# Motherboard.net
KiCad netlist of a schematic drawn in EAGLE
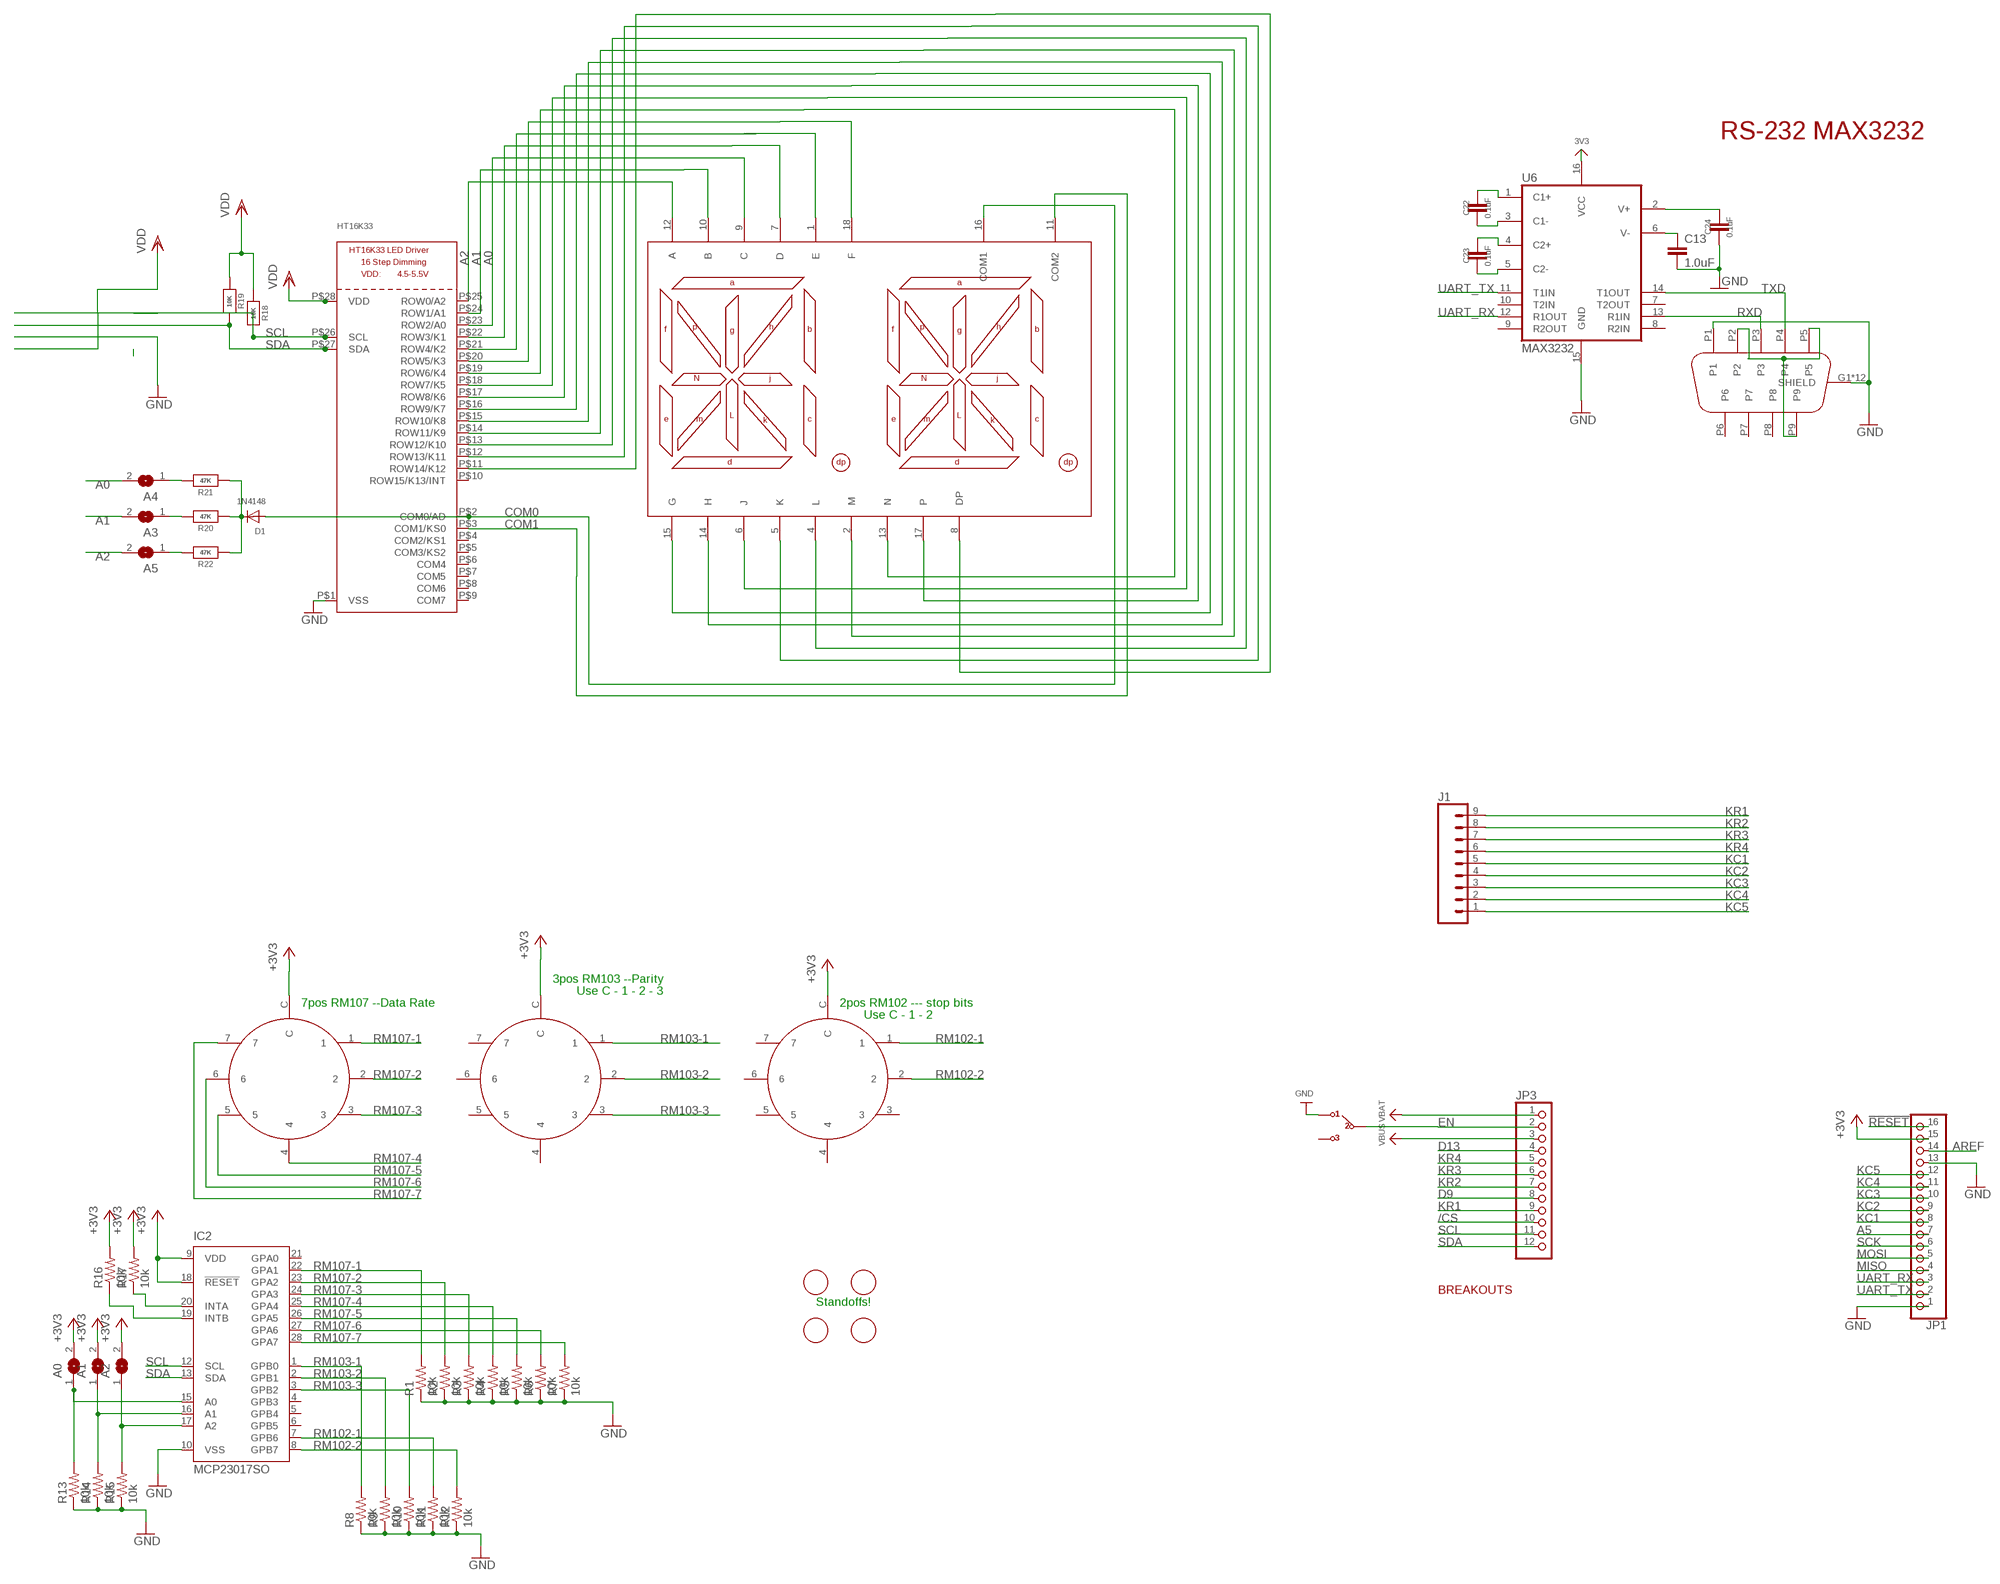
[diagram p0: schematic, sheet 1]

(export (version "E")
  (design (tool "Eeschema 10.0.6"))
  (components
    (comp (ref "A0") (value "SJ") (footprint "eagle-import:SJ") (libsource (lib "eagle-import") (part "SJ")))
    (comp (ref "A1") (value "SJ") (footprint "eagle-import:SJ") (libsource (lib "eagle-import") (part "SJ")))
    (comp (ref "A2") (value "SJ") (footprint "eagle-import:SJ") (libsource (lib "eagle-import") (part "SJ")))
    (comp (ref "A3")
      (value "SOLDERJUMPERREFLOW_NOPASTE")
      (footprint "eagle-import:SOLDERJUMPER_REFLOW_NOPASTE")
      (libsource (lib "eagle-import") (part "SOLDERJUMPERREFLOW_NOPASTE"))
    )
    (comp (ref "A4")
      (value "SOLDERJUMPERREFLOW_NOPASTE")
      (footprint "eagle-import:SOLDERJUMPER_REFLOW_NOPASTE")
      (libsource (lib "eagle-import") (part "SOLDERJUMPERREFLOW_NOPASTE"))
    )
    (comp (ref "A5")
      (value "SOLDERJUMPERREFLOW_NOPASTE")
      (footprint "eagle-import:SOLDERJUMPER_REFLOW_NOPASTE")
      (libsource (lib "eagle-import") (part "SOLDERJUMPERREFLOW_NOPASTE"))
    )
    (comp (ref "C13")
      (value "1.0uF")
      (footprint "eagle-import:0805")
      (libsource (lib "eagle-import") (part "1.0UF-0805-25V-10%"))
    )
    (comp (ref "C22")
      (value "0.1uF")
      (footprint "eagle-import:0805")
      (libsource (lib "eagle-import") (part "1.0UF-0805-25V-10%"))
    )
    (comp (ref "C23")
      (value "0.1uF")
      (footprint "eagle-import:0805")
      (libsource (lib "eagle-import") (part "1.0UF-0805-25V-10%"))
    )
    (comp (ref "C24")
      (value "0.1uF")
      (footprint "eagle-import:0805")
      (libsource (lib "eagle-import") (part "1.0UF-0805-25V-10%"))
    )
    (comp (ref "D1")
      (value "1N4148")
      (footprint "eagle-import:SOD-323F")
      (libsource (lib "eagle-import") (part "DIODESOD-323F"))
    )
    (comp (ref "DE9FEMALE")
      (value "EDGEMOUNTDE9")
      (footprint "eagle-import:DE09S065TLF")
      (libsource (lib "eagle-import") (part "EDGEMOUNTDE9"))
    )
    (comp (ref "HT16K33")
      (value "HT16K33_SOP28_SKINNY")
      (footprint "eagle-import:SOP28_300MIL_SKINNY")
      (libsource (lib "eagle-import") (part "HT16K33_SOP28_SKINNY"))
    )
    (comp (ref "IC2")
      (value "MCP23017SO")
      (footprint "eagle-import:SO28W")
      (libsource (lib "eagle-import") (part "MCP23017SO"))
    )
    (comp (ref "J1")
      (value "CONN_09")
      (footprint "eagle-import:1X09")
      (libsource (lib "eagle-import") (part "CONN_09"))
    )
    (comp (ref "JP1")
      (value "HEADER-1X16ROUND")
      (footprint "eagle-import:1X16_ROUND")
      (libsource (lib "eagle-import") (part "HEADER-1X16ROUND"))
    )
    (comp (ref "JP3")
      (value "HEADER-1X12")
      (footprint "eagle-import:1X12_ROUND")
      (libsource (lib "eagle-import") (part "HEADER-1X12"))
    )
    (comp (ref "R1")
      (value "10k")
      (footprint "eagle-import:M0805")
      (libsource (lib "eagle-import") (part "R-US_M0805"))
    )
    (comp (ref "R2")
      (value "10k")
      (footprint "eagle-import:M0805")
      (libsource (lib "eagle-import") (part "R-US_M0805"))
    )
    (comp (ref "R3")
      (value "10k")
      (footprint "eagle-import:M0805")
      (libsource (lib "eagle-import") (part "R-US_M0805"))
    )
    (comp (ref "R4")
      (value "10k")
      (footprint "eagle-import:M0805")
      (libsource (lib "eagle-import") (part "R-US_M0805"))
    )
    (comp (ref "R5")
      (value "10k")
      (footprint "eagle-import:M0805")
      (libsource (lib "eagle-import") (part "R-US_M0805"))
    )
    (comp (ref "R6")
      (value "10k")
      (footprint "eagle-import:M0805")
      (libsource (lib "eagle-import") (part "R-US_M0805"))
    )
    (comp (ref "R7")
      (value "10k")
      (footprint "eagle-import:M0805")
      (libsource (lib "eagle-import") (part "R-US_M0805"))
    )
    (comp (ref "R8")
      (value "10k")
      (footprint "eagle-import:M0805")
      (libsource (lib "eagle-import") (part "R-US_M0805"))
    )
    (comp (ref "R9")
      (value "10k")
      (footprint "eagle-import:M0805")
      (libsource (lib "eagle-import") (part "R-US_M0805"))
    )
    (comp (ref "R10")
      (value "10k")
      (footprint "eagle-import:M0805")
      (libsource (lib "eagle-import") (part "R-US_M0805"))
    )
    (comp (ref "R11")
      (value "10k")
      (footprint "eagle-import:M0805")
      (libsource (lib "eagle-import") (part "R-US_M0805"))
    )
    (comp (ref "R12")
      (value "10k")
      (footprint "eagle-import:M0805")
      (libsource (lib "eagle-import") (part "R-US_M0805"))
    )
    (comp (ref "R13")
      (value "10k")
      (footprint "eagle-import:M0805")
      (libsource (lib "eagle-import") (part "R-US_M0805"))
    )
    (comp (ref "R14")
      (value "10k")
      (footprint "eagle-import:M0805")
      (libsource (lib "eagle-import") (part "R-US_M0805"))
    )
    (comp (ref "R15")
      (value "10k")
      (footprint "eagle-import:M0805")
      (libsource (lib "eagle-import") (part "R-US_M0805"))
    )
    (comp (ref "R16")
      (value "10k")
      (footprint "eagle-import:M0805")
      (libsource (lib "eagle-import") (part "R-US_M0805"))
    )
    (comp (ref "R17")
      (value "10k")
      (footprint "eagle-import:M0805")
      (libsource (lib "eagle-import") (part "R-US_M0805"))
    )
    (comp (ref "R18")
      (value "10K")
      (footprint "eagle-import:0805-NO")
      (libsource (lib "eagle-import") (part "RESISTOR0805_NOOUTLINE"))
    )
    (comp (ref "R19")
      (value "10K")
      (footprint "eagle-import:0805-NO")
      (libsource (lib "eagle-import") (part "RESISTOR0805_NOOUTLINE"))
    )
    (comp (ref "R20")
      (value "47K")
      (footprint "eagle-import:0805-NO")
      (libsource (lib "eagle-import") (part "RESISTOR0805_NOOUTLINE"))
    )
    (comp (ref "R21")
      (value "47K")
      (footprint "eagle-import:0805-NO")
      (libsource (lib "eagle-import") (part "RESISTOR0805_NOOUTLINE"))
    )
    (comp (ref "R22")
      (value "47K")
      (footprint "eagle-import:0805-NO")
      (libsource (lib "eagle-import") (part "RESISTOR0805_NOOUTLINE"))
    )
    (comp (ref "U$1")
      (value "HDSP-A27C")
      (footprint "eagle-import:DIP-18")
      (libsource (lib "eagle-import") (part "HDSP-A27C"))
    )
    (comp (ref "U$2")
      (value "RM107772BCB")
      (footprint "eagle-import:RM107772BCB")
      (libsource (lib "eagle-import") (part "RM107772BCB"))
    )
    (comp (ref "U$3")
      (value "RM107772BCB")
      (footprint "eagle-import:RM107772BCB")
      (libsource (lib "eagle-import") (part "RM107772BCB"))
    )
    (comp (ref "U$5")
      (value "OS102011MA1QN1")
      (footprint "eagle-import:OS102011MA1QN1")
      (libsource (lib "eagle-import") (part "OS102011MA1QN1"))
    )
    (comp (ref "U$6")
      (value "RM107772BCB")
      (footprint "eagle-import:RM107772BCB")
      (libsource (lib "eagle-import") (part "RM107772BCB"))
    )
    (comp (ref "U$7")
      (value "KEYSTONESTANDOFF")
      (footprint "eagle-import:KEYSTONESTANDOFF")
      (libsource (lib "eagle-import") (part "KEYSTONESTANDOFF"))
    )
    (comp (ref "U$8")
      (value "KEYSTONESTANDOFF")
      (footprint "eagle-import:KEYSTONESTANDOFF")
      (libsource (lib "eagle-import") (part "KEYSTONESTANDOFF"))
    )
    (comp (ref "U$9")
      (value "KEYSTONESTANDOFF")
      (footprint "eagle-import:KEYSTONESTANDOFF")
      (libsource (lib "eagle-import") (part "KEYSTONESTANDOFF"))
    )
    (comp (ref "U$10")
      (value "KEYSTONESTANDOFF")
      (footprint "eagle-import:KEYSTONESTANDOFF")
      (libsource (lib "eagle-import") (part "KEYSTONESTANDOFF"))
    )
    (comp (ref "U6")
      (value "MAX3232")
      (footprint "eagle-import:SO16")
      (libsource (lib "eagle-import") (part "MAX2323SOIC16"))
    )
  )
  (nets
    (net (code "1") (name "+3V3") (class "Default")
      (node (ref "A0") (pin "2") (pinfunction "2_2") (pintype "passive"))
      (node (ref "A1") (pin "2") (pinfunction "2_2") (pintype "passive"))
      (node (ref "A2") (pin "2") (pinfunction "2_2") (pintype "passive"))
      (node (ref "IC2") (pin "18") (pinfunction "~{RESET}_18") (pintype "input"))
      (node (ref "IC2") (pin "9") (pinfunction "VDD_9") (pintype "power_in"))
      (node (ref "JP1") (pin "15") (pinfunction "15_15") (pintype "passive"))
      (node (ref "R16") (pin "2") (pinfunction "2_2") (pintype "passive"))
      (node (ref "R17") (pin "2") (pinfunction "2_2") (pintype "passive"))
      (node (ref "U$2") (pin "C") (pinfunction "C_C") (pintype "bidirectional"))
      (node (ref "U$3") (pin "C") (pinfunction "C_C") (pintype "bidirectional"))
      (node (ref "U$6") (pin "C") (pinfunction "C_C") (pintype "bidirectional"))
    )
    (net (code "2") (name "/A0") (class "Default")
      (node (ref "A4") (pin "2") (pinfunction "2_2") (pintype "passive"))
      (node (ref "HT16K33") (pin "P$23") (pinfunction "ROW2/A0_P$23") (pintype "bidirectional"))
      (node (ref "U$1") (pin "9") (pinfunction "C_9") (pintype "bidirectional"))
    )
    (net (code "3") (name "/A1") (class "Default")
      (node (ref "A3") (pin "2") (pinfunction "2_2") (pintype "passive"))
      (node (ref "HT16K33") (pin "P$24") (pinfunction "ROW1/A1_P$24") (pintype "bidirectional"))
      (node (ref "U$1") (pin "10") (pinfunction "B_10") (pintype "bidirectional"))
    )
    (net (code "4") (name "/A2") (class "Default")
      (node (ref "A5") (pin "2") (pinfunction "2_2") (pintype "passive"))
      (node (ref "HT16K33") (pin "P$25") (pinfunction "ROW0/A2_P$25") (pintype "bidirectional"))
      (node (ref "U$1") (pin "12") (pinfunction "A_12") (pintype "bidirectional"))
    )
    (net (code "5") (name "/A5") (class "Default")
      (node (ref "JP1") (pin "7") (pinfunction "7_7") (pintype "passive"))
    )
    (net (code "6") (name "/AREF") (class "Default")
      (node (ref "JP1") (pin "14") (pinfunction "14_14") (pintype "passive"))
    )
    (net (code "7") (name "/COM0") (class "Default")
      (node (ref "D1") (pin "A") (pinfunction "A_A") (pintype "passive"))
      (node (ref "HT16K33") (pin "P$2") (pinfunction "COM0/AD_P$2") (pintype "bidirectional"))
      (node (ref "U$1") (pin "16") (pinfunction "COM1_16") (pintype "bidirectional"))
    )
    (net (code "8") (name "/COM1") (class "Default")
      (node (ref "HT16K33") (pin "P$3") (pinfunction "COM1/KS0_P$3") (pintype "bidirectional"))
      (node (ref "U$1") (pin "11") (pinfunction "COM2_11") (pintype "bidirectional"))
    )
    (net (code "9") (name "/D9") (class "Default")
      (node (ref "JP3") (pin "8") (pinfunction "8_8") (pintype "passive"))
    )
    (net (code "10") (name "/D13") (class "Default")
      (node (ref "JP3") (pin "4") (pinfunction "4_4") (pintype "passive"))
    )
    (net (code "11") (name "/EN") (class "Default")
      (node (ref "JP3") (pin "2") (pinfunction "2_2") (pintype "passive"))
      (node (ref "U$5") (pin "P$2") (pinfunction "P$2_P$2") (pintype "bidirectional"))
    )
    (net (code "12") (name "/KC1") (class "Default")
      (node (ref "J1") (pin "5") (pinfunction "5_5") (pintype "passive"))
      (node (ref "JP1") (pin "8") (pinfunction "8_8") (pintype "passive"))
    )
    (net (code "13") (name "/KC2") (class "Default")
      (node (ref "J1") (pin "4") (pinfunction "4_4") (pintype "passive"))
      (node (ref "JP1") (pin "9") (pinfunction "9_9") (pintype "passive"))
    )
    (net (code "14") (name "/KC3") (class "Default")
      (node (ref "J1") (pin "3") (pinfunction "3_3") (pintype "passive"))
      (node (ref "JP1") (pin "10") (pinfunction "10_10") (pintype "passive"))
    )
    (net (code "15") (name "/KC4") (class "Default")
      (node (ref "J1") (pin "2") (pinfunction "2_2") (pintype "passive"))
      (node (ref "JP1") (pin "11") (pinfunction "11_11") (pintype "passive"))
    )
    (net (code "16") (name "/KC5") (class "Default")
      (node (ref "J1") (pin "1") (pinfunction "1_1") (pintype "passive"))
      (node (ref "JP1") (pin "12") (pinfunction "12_12") (pintype "passive"))
    )
    (net (code "17") (name "/KR1") (class "Default")
      (node (ref "J1") (pin "9") (pinfunction "9_9") (pintype "passive"))
      (node (ref "JP3") (pin "9") (pinfunction "9_9") (pintype "passive"))
    )
    (net (code "18") (name "/KR2") (class "Default")
      (node (ref "J1") (pin "8") (pinfunction "8_8") (pintype "passive"))
      (node (ref "JP3") (pin "7") (pinfunction "7_7") (pintype "passive"))
    )
    (net (code "19") (name "/KR3") (class "Default")
      (node (ref "J1") (pin "7") (pinfunction "7_7") (pintype "passive"))
      (node (ref "JP3") (pin "6") (pinfunction "6_6") (pintype "passive"))
    )
    (net (code "20") (name "/KR4") (class "Default")
      (node (ref "J1") (pin "6") (pinfunction "6_6") (pintype "passive"))
      (node (ref "JP3") (pin "5") (pinfunction "5_5") (pintype "passive"))
    )
    (net (code "21") (name "/MISO") (class "Default")
      (node (ref "JP1") (pin "4") (pinfunction "4_4") (pintype "passive"))
    )
    (net (code "22") (name "/MOSI") (class "Default")
      (node (ref "JP1") (pin "5") (pinfunction "5_5") (pintype "passive"))
    )
    (net (code "23") (name "/RM102-1") (class "Default")
      (node (ref "IC2") (pin "7") (pinfunction "GPB6_7") (pintype "bidirectional"))
      (node (ref "R11") (pin "2") (pinfunction "2_2") (pintype "passive"))
      (node (ref "U$6") (pin "1") (pinfunction "1_1") (pintype "bidirectional"))
    )
    (net (code "24") (name "/RM102-2") (class "Default")
      (node (ref "IC2") (pin "8") (pinfunction "GPB7_8") (pintype "bidirectional"))
      (node (ref "R12") (pin "2") (pinfunction "2_2") (pintype "passive"))
      (node (ref "U$6") (pin "2") (pinfunction "2_2") (pintype "bidirectional"))
    )
    (net (code "25") (name "/RM103-1") (class "Default")
      (node (ref "IC2") (pin "1") (pinfunction "GPB0_1") (pintype "bidirectional"))
      (node (ref "R8") (pin "2") (pinfunction "2_2") (pintype "passive"))
      (node (ref "U$3") (pin "1") (pinfunction "1_1") (pintype "bidirectional"))
    )
    (net (code "26") (name "/RM103-2") (class "Default")
      (node (ref "IC2") (pin "2") (pinfunction "GPB1_2") (pintype "bidirectional"))
      (node (ref "R9") (pin "2") (pinfunction "2_2") (pintype "passive"))
      (node (ref "U$3") (pin "2") (pinfunction "2_2") (pintype "bidirectional"))
    )
    (net (code "27") (name "/RM103-3") (class "Default")
      (node (ref "IC2") (pin "3") (pinfunction "GPB2_3") (pintype "bidirectional"))
      (node (ref "R10") (pin "2") (pinfunction "2_2") (pintype "passive"))
      (node (ref "U$3") (pin "3") (pinfunction "3_3") (pintype "bidirectional"))
    )
    (net (code "28") (name "/RM107-1") (class "Default")
      (node (ref "IC2") (pin "22") (pinfunction "GPA1_22") (pintype "bidirectional"))
      (node (ref "R1") (pin "2") (pinfunction "2_2") (pintype "passive"))
      (node (ref "U$2") (pin "1") (pinfunction "1_1") (pintype "bidirectional"))
    )
    (net (code "29") (name "/RM107-2") (class "Default")
      (node (ref "IC2") (pin "23") (pinfunction "GPA2_23") (pintype "bidirectional"))
      (node (ref "R2") (pin "2") (pinfunction "2_2") (pintype "passive"))
      (node (ref "U$2") (pin "2") (pinfunction "2_2") (pintype "bidirectional"))
    )
    (net (code "30") (name "/RM107-3") (class "Default")
      (node (ref "IC2") (pin "24") (pinfunction "GPA3_24") (pintype "bidirectional"))
      (node (ref "R3") (pin "2") (pinfunction "2_2") (pintype "passive"))
      (node (ref "U$2") (pin "3") (pinfunction "3_3") (pintype "bidirectional"))
    )
    (net (code "31") (name "/RM107-4") (class "Default")
      (node (ref "IC2") (pin "25") (pinfunction "GPA4_25") (pintype "bidirectional"))
      (node (ref "R4") (pin "2") (pinfunction "2_2") (pintype "passive"))
      (node (ref "U$2") (pin "4") (pinfunction "4_4") (pintype "bidirectional"))
    )
    (net (code "32") (name "/RM107-5") (class "Default")
      (node (ref "IC2") (pin "26") (pinfunction "GPA5_26") (pintype "bidirectional"))
      (node (ref "R5") (pin "2") (pinfunction "2_2") (pintype "passive"))
      (node (ref "U$2") (pin "5") (pinfunction "5_5") (pintype "bidirectional"))
    )
    (net (code "33") (name "/RM107-6") (class "Default")
      (node (ref "IC2") (pin "27") (pinfunction "GPA6_27") (pintype "bidirectional"))
      (node (ref "R6") (pin "2") (pinfunction "2_2") (pintype "passive"))
      (node (ref "U$2") (pin "6") (pinfunction "6_6") (pintype "bidirectional"))
    )
    (net (code "34") (name "/RM107-7") (class "Default")
      (node (ref "IC2") (pin "28") (pinfunction "GPA7_28") (pintype "bidirectional"))
      (node (ref "R7") (pin "2") (pinfunction "2_2") (pintype "passive"))
      (node (ref "U$2") (pin "7") (pinfunction "7_7") (pintype "bidirectional"))
    )
    (net (code "35") (name "/RXD") (class "Default")
      (node (ref "DE9FEMALE") (pin "P3") (pinfunction "P3_P3") (pintype "bidirectional"))
      (node (ref "U6") (pin "13") (pinfunction "R1IN_13") (pintype "input"))
    )
    (net (code "36") (name "/SCK") (class "Default")
      (node (ref "JP1") (pin "6") (pinfunction "6_6") (pintype "passive"))
    )
    (net (code "37") (name "/SCL") (class "Default")
      (node (ref "HT16K33") (pin "P$26") (pinfunction "SCL_P$26") (pintype "bidirectional"))
      (node (ref "IC2") (pin "12") (pinfunction "SCL_12") (pintype "input"))
      (node (ref "JP3") (pin "11") (pinfunction "11_11") (pintype "passive"))
      (node (ref "R18") (pin "2") (pinfunction "2_2") (pintype "passive"))
    )
    (net (code "38") (name "/SDA") (class "Default")
      (node (ref "HT16K33") (pin "P$27") (pinfunction "SDA_P$27") (pintype "bidirectional"))
      (node (ref "IC2") (pin "13") (pinfunction "SDA_13") (pintype "bidirectional"))
      (node (ref "JP3") (pin "12") (pinfunction "12_12") (pintype "passive"))
      (node (ref "R19") (pin "2") (pinfunction "2_2") (pintype "passive"))
    )
    (net (code "39") (name "/TXD") (class "Default")
      (node (ref "DE9FEMALE") (pin "P4") (pinfunction "P4_P4") (pintype "bidirectional"))
      (node (ref "U6") (pin "14") (pinfunction "T1OUT_14") (pintype "output"))
    )
    (net (code "40") (name "/UART_RX") (class "Default")
      (node (ref "JP1") (pin "3") (pinfunction "3_3") (pintype "passive"))
      (node (ref "U6") (pin "12") (pinfunction "R1OUT_12") (pintype "output"))
    )
    (net (code "41") (name "/UART_TX") (class "Default")
      (node (ref "JP1") (pin "2") (pinfunction "2_2") (pintype "passive"))
      (node (ref "U6") (pin "11") (pinfunction "T1IN_11") (pintype "input"))
    )
    (net (code "42") (name "/{slash}CS") (class "Default")
      (node (ref "JP3") (pin "10") (pinfunction "10_10") (pintype "passive"))
    )
    (net (code "43") (name "/~{RESET}") (class "Default")
      (node (ref "JP1") (pin "16") (pinfunction "16_16") (pintype "passive"))
    )
    (net (code "44") (name "3V3") (class "Default")
      (node (ref "U6") (pin "16") (pinfunction "VCC_16") (pintype "bidirectional"))
    )
    (net (code "45") (name "GND") (class "Default")
      (node (ref "C13") (pin "2") (pinfunction "2_2") (pintype "passive"))
      (node (ref "C24") (pin "2") (pinfunction "2_2") (pintype "passive"))
      (node (ref "DE9FEMALE") (pin "G1") (pinfunction "SHIELD_G1") (pintype "bidirectional"))
      (node (ref "DE9FEMALE") (pin "G10") (pinfunction "SHIELD_G10") (pintype "bidirectional"))
      (node (ref "DE9FEMALE") (pin "G11") (pinfunction "SHIELD_G11") (pintype "bidirectional"))
      (node (ref "DE9FEMALE") (pin "G12") (pinfunction "SHIELD_G12") (pintype "bidirectional"))
      (node (ref "DE9FEMALE") (pin "G2") (pinfunction "SHIELD_G2") (pintype "bidirectional"))
      (node (ref "DE9FEMALE") (pin "G3") (pinfunction "SHIELD_G3") (pintype "bidirectional"))
      (node (ref "DE9FEMALE") (pin "G4") (pinfunction "SHIELD_G4") (pintype "bidirectional"))
      (node (ref "DE9FEMALE") (pin "G5") (pinfunction "SHIELD_G5") (pintype "bidirectional"))
      (node (ref "DE9FEMALE") (pin "G6") (pinfunction "SHIELD_G6") (pintype "bidirectional"))
      (node (ref "DE9FEMALE") (pin "G7") (pinfunction "SHIELD_G7") (pintype "bidirectional"))
      (node (ref "DE9FEMALE") (pin "G8") (pinfunction "SHIELD_G8") (pintype "bidirectional"))
      (node (ref "DE9FEMALE") (pin "G9") (pinfunction "SHIELD_G9") (pintype "bidirectional"))
      (node (ref "DE9FEMALE") (pin "P1") (pinfunction "P1_P1") (pintype "bidirectional"))
      (node (ref "HT16K33") (pin "P$1") (pinfunction "VSS_P$1") (pintype "bidirectional"))
      (node (ref "IC2") (pin "10") (pinfunction "VSS_10") (pintype "power_in"))
      (node (ref "JP1") (pin "1") (pinfunction "1_1") (pintype "passive"))
      (node (ref "JP1") (pin "13") (pinfunction "13_13") (pintype "passive"))
      (node (ref "R1") (pin "1") (pinfunction "1_1") (pintype "passive"))
      (node (ref "R10") (pin "1") (pinfunction "1_1") (pintype "passive"))
      (node (ref "R11") (pin "1") (pinfunction "1_1") (pintype "passive"))
      (node (ref "R12") (pin "1") (pinfunction "1_1") (pintype "passive"))
      (node (ref "R13") (pin "1") (pinfunction "1_1") (pintype "passive"))
      (node (ref "R14") (pin "1") (pinfunction "1_1") (pintype "passive"))
      (node (ref "R15") (pin "1") (pinfunction "1_1") (pintype "passive"))
      (node (ref "R2") (pin "1") (pinfunction "1_1") (pintype "passive"))
      (node (ref "R3") (pin "1") (pinfunction "1_1") (pintype "passive"))
      (node (ref "R4") (pin "1") (pinfunction "1_1") (pintype "passive"))
      (node (ref "R5") (pin "1") (pinfunction "1_1") (pintype "passive"))
      (node (ref "R6") (pin "1") (pinfunction "1_1") (pintype "passive"))
      (node (ref "R7") (pin "1") (pinfunction "1_1") (pintype "passive"))
      (node (ref "R8") (pin "1") (pinfunction "1_1") (pintype "passive"))
      (node (ref "R9") (pin "1") (pinfunction "1_1") (pintype "passive"))
      (node (ref "U$5") (pin "P$1") (pinfunction "P$1_P$1") (pintype "bidirectional"))
      (node (ref "U6") (pin "15") (pinfunction "GND_15") (pintype "bidirectional"))
    )
    (net (code "46") (name "Net-(A3-Pad1)") (class "Default")
      (node (ref "A3") (pin "1") (pinfunction "1_1") (pintype "passive"))
      (node (ref "R20") (pin "2") (pinfunction "2_2") (pintype "passive"))
    )
    (net (code "47") (name "Net-(A4-Pad1)") (class "Default")
      (node (ref "A4") (pin "1") (pinfunction "1_1") (pintype "passive"))
      (node (ref "R21") (pin "2") (pinfunction "2_2") (pintype "passive"))
    )
    (net (code "48") (name "Net-(A5-Pad1)") (class "Default")
      (node (ref "A5") (pin "1") (pinfunction "1_1") (pintype "passive"))
      (node (ref "R22") (pin "2") (pinfunction "2_2") (pintype "passive"))
    )
    (net (code "49") (name "Net-(D1-PadC)") (class "Default")
      (node (ref "D1") (pin "C") (pinfunction "C_C") (pintype "passive"))
      (node (ref "R20") (pin "1") (pinfunction "1_1") (pintype "passive"))
      (node (ref "R21") (pin "1") (pinfunction "1_1") (pintype "passive"))
      (node (ref "R22") (pin "1") (pinfunction "1_1") (pintype "passive"))
    )
    (net (code "50") (name "Net-(DE9FEMALE-PadP2)") (class "Default")
      (node (ref "DE9FEMALE") (pin "P2") (pinfunction "P2_P2") (pintype "bidirectional"))
      (node (ref "DE9FEMALE") (pin "P5") (pinfunction "P5_P5") (pintype "bidirectional"))
      (node (ref "DE9FEMALE") (pin "P9") (pinfunction "P9_P9") (pintype "bidirectional"))
    )
    (net (code "51") (name "Net-(HT16K33-ROW3{slash}K1)") (class "Default")
      (node (ref "HT16K33") (pin "P$22") (pinfunction "ROW3/K1_P$22") (pintype "bidirectional"))
      (node (ref "U$1") (pin "7") (pinfunction "D_7") (pintype "bidirectional"))
    )
    (net (code "52") (name "Net-(HT16K33-ROW4{slash}K2)") (class "Default")
      (node (ref "HT16K33") (pin "P$21") (pinfunction "ROW4/K2_P$21") (pintype "bidirectional"))
      (node (ref "U$1") (pin "1") (pinfunction "E_1") (pintype "bidirectional"))
    )
    (net (code "53") (name "Net-(HT16K33-ROW5{slash}K3)") (class "Default")
      (node (ref "HT16K33") (pin "P$20") (pinfunction "ROW5/K3_P$20") (pintype "bidirectional"))
      (node (ref "U$1") (pin "18") (pinfunction "F_18") (pintype "bidirectional"))
    )
    (net (code "54") (name "Net-(HT16K33-ROW6{slash}K4)") (class "Default")
      (node (ref "HT16K33") (pin "P$19") (pinfunction "ROW6/K4_P$19") (pintype "bidirectional"))
      (node (ref "U$1") (pin "13") (pinfunction "N_13") (pintype "bidirectional"))
    )
    (net (code "55") (name "Net-(HT16K33-ROW7{slash}K5)") (class "Default")
      (node (ref "HT16K33") (pin "P$18") (pinfunction "ROW7/K5_P$18") (pintype "bidirectional"))
      (node (ref "U$1") (pin "6") (pinfunction "J_6") (pintype "bidirectional"))
    )
    (net (code "56") (name "Net-(HT16K33-ROW8{slash}K6)") (class "Default")
      (node (ref "HT16K33") (pin "P$17") (pinfunction "ROW8/K6_P$17") (pintype "bidirectional"))
      (node (ref "U$1") (pin "17") (pinfunction "P_17") (pintype "bidirectional"))
    )
    (net (code "57") (name "Net-(HT16K33-ROW9{slash}K7)") (class "Default")
      (node (ref "HT16K33") (pin "P$16") (pinfunction "ROW9/K7_P$16") (pintype "bidirectional"))
      (node (ref "U$1") (pin "15") (pinfunction "G_15") (pintype "bidirectional"))
    )
    (net (code "58") (name "Net-(HT16K33-ROW10{slash}K8)") (class "Default")
      (node (ref "HT16K33") (pin "P$15") (pinfunction "ROW10/K8_P$15") (pintype "bidirectional"))
      (node (ref "U$1") (pin "14") (pinfunction "H_14") (pintype "bidirectional"))
    )
    (net (code "59") (name "Net-(HT16K33-ROW11{slash}K9)") (class "Default")
      (node (ref "HT16K33") (pin "P$14") (pinfunction "ROW11/K9_P$14") (pintype "bidirectional"))
      (node (ref "U$1") (pin "2") (pinfunction "M_2") (pintype "bidirectional"))
    )
    (net (code "60") (name "Net-(HT16K33-ROW12{slash}K10)") (class "Default")
      (node (ref "HT16K33") (pin "P$13") (pinfunction "ROW12/K10_P$13") (pintype "bidirectional"))
      (node (ref "U$1") (pin "4") (pinfunction "L_4") (pintype "bidirectional"))
    )
    (net (code "61") (name "Net-(HT16K33-ROW13{slash}K11)") (class "Default")
      (node (ref "HT16K33") (pin "P$12") (pinfunction "ROW13/K11_P$12") (pintype "bidirectional"))
      (node (ref "U$1") (pin "5") (pinfunction "K_5") (pintype "bidirectional"))
    )
    (net (code "62") (name "Net-(HT16K33-ROW14{slash}K12)") (class "Default")
      (node (ref "HT16K33") (pin "P$11") (pinfunction "ROW14/K12_P$11") (pintype "bidirectional"))
      (node (ref "U$1") (pin "8") (pinfunction "DP_8") (pintype "bidirectional"))
    )
    (net (code "63") (name "Net-(IC2-A0)") (class "Default")
      (node (ref "A0") (pin "1") (pinfunction "1_1") (pintype "passive"))
      (node (ref "IC2") (pin "15") (pinfunction "A0_15") (pintype "input"))
      (node (ref "R13") (pin "2") (pinfunction "2_2") (pintype "passive"))
    )
    (net (code "64") (name "Net-(IC2-A1)") (class "Default")
      (node (ref "A1") (pin "1") (pinfunction "1_1") (pintype "passive"))
      (node (ref "IC2") (pin "16") (pinfunction "A1_16") (pintype "input"))
      (node (ref "R14") (pin "2") (pinfunction "2_2") (pintype "passive"))
    )
    (net (code "65") (name "Net-(IC2-A2)") (class "Default")
      (node (ref "A2") (pin "1") (pinfunction "1_1") (pintype "passive"))
      (node (ref "IC2") (pin "17") (pinfunction "A2_17") (pintype "input"))
      (node (ref "R15") (pin "2") (pinfunction "2_2") (pintype "passive"))
    )
    (net (code "66") (name "Net-(IC2-INTA)") (class "Default")
      (node (ref "IC2") (pin "20") (pinfunction "INTA_20") (pintype "output"))
      (node (ref "R17") (pin "1") (pinfunction "1_1") (pintype "passive"))
    )
    (net (code "67") (name "Net-(IC2-INTB)") (class "Default")
      (node (ref "IC2") (pin "19") (pinfunction "INTB_19") (pintype "output"))
      (node (ref "R16") (pin "1") (pinfunction "1_1") (pintype "passive"))
    )
    (net (code "68") (name "Net-(U6-C1+)") (class "Default")
      (node (ref "C22") (pin "1") (pinfunction "1_1") (pintype "passive"))
      (node (ref "U6") (pin "1") (pinfunction "C1+_1") (pintype "bidirectional"))
    )
    (net (code "69") (name "Net-(U6-C1-)") (class "Default")
      (node (ref "C22") (pin "2") (pinfunction "2_2") (pintype "passive"))
      (node (ref "U6") (pin "3") (pinfunction "C1-_3") (pintype "bidirectional"))
    )
    (net (code "70") (name "Net-(U6-C2+)") (class "Default")
      (node (ref "C23") (pin "1") (pinfunction "1_1") (pintype "passive"))
      (node (ref "U6") (pin "4") (pinfunction "C2+_4") (pintype "bidirectional"))
    )
    (net (code "71") (name "Net-(U6-C2-)") (class "Default")
      (node (ref "C23") (pin "2") (pinfunction "2_2") (pintype "passive"))
      (node (ref "U6") (pin "5") (pinfunction "C2-_5") (pintype "bidirectional"))
    )
    (net (code "72") (name "Net-(U6-V+)") (class "Default")
      (node (ref "C24") (pin "1") (pinfunction "1_1") (pintype "passive"))
      (node (ref "U6") (pin "2") (pinfunction "V+_2") (pintype "bidirectional"))
    )
    (net (code "73") (name "Net-(U6-V-)") (class "Default")
      (node (ref "C13") (pin "1") (pinfunction "1_1") (pintype "passive"))
      (node (ref "U6") (pin "6") (pinfunction "V-_6") (pintype "bidirectional"))
    )
    (net (code "74") (name "VBAT") (class "Default")
      (node (ref "JP3") (pin "1") (pinfunction "1_1") (pintype "passive"))
    )
    (net (code "75") (name "VBUS") (class "Default")
      (node (ref "JP3") (pin "3") (pinfunction "3_3") (pintype "passive"))
    )
    (net (code "76") (name "VDD") (class "Default")
      (node (ref "HT16K33") (pin "P$28") (pinfunction "VDD_P$28") (pintype "bidirectional"))
      (node (ref "R18") (pin "1") (pinfunction "1_1") (pintype "passive"))
      (node (ref "R19") (pin "1") (pinfunction "1_1") (pintype "passive"))
    )
    (net (code "77") (name "unconnected-(DE9FEMALE-PadP6)") (class "Default")
      (node (ref "DE9FEMALE") (pin "P6") (pinfunction "P6_P6") (pintype "bidirectional"))
    )
    (net (code "78") (name "unconnected-(DE9FEMALE-PadP7)") (class "Default")
      (node (ref "DE9FEMALE") (pin "P7") (pinfunction "P7_P7") (pintype "bidirectional"))
    )
    (net (code "79") (name "unconnected-(DE9FEMALE-PadP8)") (class "Default")
      (node (ref "DE9FEMALE") (pin "P8") (pinfunction "P8_P8") (pintype "bidirectional"))
    )
    (net (code "80") (name "unconnected-(HT16K33-COM2{slash}KS1-PadP$4)") (class "Default")
      (node (ref "HT16K33") (pin "P$4") (pinfunction "COM2/KS1_P$4") (pintype "bidirectional"))
    )
    (net (code "81") (name "unconnected-(HT16K33-COM3{slash}KS2-PadP$5)") (class "Default")
      (node (ref "HT16K33") (pin "P$5") (pinfunction "COM3/KS2_P$5") (pintype "bidirectional"))
    )
    (net (code "82") (name "unconnected-(HT16K33-COM4-PadP$6)") (class "Default")
      (node (ref "HT16K33") (pin "P$6") (pinfunction "COM4_P$6") (pintype "bidirectional"))
    )
    (net (code "83") (name "unconnected-(HT16K33-COM5-PadP$7)") (class "Default")
      (node (ref "HT16K33") (pin "P$7") (pinfunction "COM5_P$7") (pintype "bidirectional"))
    )
    (net (code "84") (name "unconnected-(HT16K33-COM6-PadP$8)") (class "Default")
      (node (ref "HT16K33") (pin "P$8") (pinfunction "COM6_P$8") (pintype "bidirectional"))
    )
    (net (code "85") (name "unconnected-(HT16K33-COM7-PadP$9)") (class "Default")
      (node (ref "HT16K33") (pin "P$9") (pinfunction "COM7_P$9") (pintype "bidirectional"))
    )
    (net (code "86") (name "unconnected-(HT16K33-ROW15{slash}K13{slash}INT-PadP$10)") (class "Default")
      (node (ref "HT16K33") (pin "P$10") (pinfunction "ROW15/K13/INT_P$10") (pintype "bidirectional"))
    )
    (net (code "87") (name "unconnected-(IC2-GPA0-Pad21)") (class "Default")
      (node (ref "IC2") (pin "21") (pinfunction "GPA0_21") (pintype "bidirectional"))
    )
    (net (code "88") (name "unconnected-(IC2-GPB3-Pad4)") (class "Default")
      (node (ref "IC2") (pin "4") (pinfunction "GPB3_4") (pintype "bidirectional"))
    )
    (net (code "89") (name "unconnected-(IC2-GPB4-Pad5)") (class "Default")
      (node (ref "IC2") (pin "5") (pinfunction "GPB4_5") (pintype "bidirectional"))
    )
    (net (code "90") (name "unconnected-(IC2-GPB5-Pad6)") (class "Default")
      (node (ref "IC2") (pin "6") (pinfunction "GPB5_6") (pintype "bidirectional"))
    )
    (net (code "91") (name "unconnected-(U$3-Pad4)") (class "Default")
      (node (ref "U$3") (pin "4") (pinfunction "4_4") (pintype "bidirectional"))
    )
    (net (code "92") (name "unconnected-(U$3-Pad5)") (class "Default")
      (node (ref "U$3") (pin "5") (pinfunction "5_5") (pintype "bidirectional"))
    )
    (net (code "93") (name "unconnected-(U$3-Pad6)") (class "Default")
      (node (ref "U$3") (pin "6") (pinfunction "6_6") (pintype "bidirectional"))
    )
    (net (code "94") (name "unconnected-(U$3-Pad7)") (class "Default")
      (node (ref "U$3") (pin "7") (pinfunction "7_7") (pintype "bidirectional"))
    )
    (net (code "95") (name "unconnected-(U$5-CASE-PadCASE1)") (class "Default")
      (node (ref "U$5") (pin "CASE1") (pinfunction "CASE_CASE1") (pintype "no_connect"))
    )
    (net (code "96") (name "unconnected-(U$5-CASE-PadCASE2)") (class "Default")
      (node (ref "U$5") (pin "CASE2") (pinfunction "CASE_CASE2") (pintype "no_connect"))
    )
    (net (code "97") (name "unconnected-(U$5-PadP$3)") (class "Default")
      (node (ref "U$5") (pin "P$3") (pinfunction "P$3_P$3") (pintype "bidirectional"))
    )
    (net (code "98") (name "unconnected-(U$6-Pad3)") (class "Default")
      (node (ref "U$6") (pin "3") (pinfunction "3_3") (pintype "bidirectional"))
    )
    (net (code "99") (name "unconnected-(U$6-Pad4)") (class "Default")
      (node (ref "U$6") (pin "4") (pinfunction "4_4") (pintype "bidirectional"))
    )
    (net (code "100") (name "unconnected-(U$6-Pad5)") (class "Default")
      (node (ref "U$6") (pin "5") (pinfunction "5_5") (pintype "bidirectional"))
    )
    (net (code "101") (name "unconnected-(U$6-Pad6)") (class "Default")
      (node (ref "U$6") (pin "6") (pinfunction "6_6") (pintype "bidirectional"))
    )
    (net (code "102") (name "unconnected-(U$6-Pad7)") (class "Default")
      (node (ref "U$6") (pin "7") (pinfunction "7_7") (pintype "bidirectional"))
    )
    (net (code "103") (name "unconnected-(U6-R2IN-Pad8)") (class "Default")
      (node (ref "U6") (pin "8") (pinfunction "R2IN_8") (pintype "input"))
    )
    (net (code "104") (name "unconnected-(U6-R2OUT-Pad9)") (class "Default")
      (node (ref "U6") (pin "9") (pinfunction "R2OUT_9") (pintype "output"))
    )
    (net (code "105") (name "unconnected-(U6-T2IN-Pad10)") (class "Default")
      (node (ref "U6") (pin "10") (pinfunction "T2IN_10") (pintype "input"))
    )
    (net (code "106") (name "unconnected-(U6-T2OUT-Pad7)") (class "Default")
      (node (ref "U6") (pin "7") (pinfunction "T2OUT_7") (pintype "output"))
    )
  )
)
